# sensorCO2.net
KiCad netlist of a schematic drawn in EAGLE
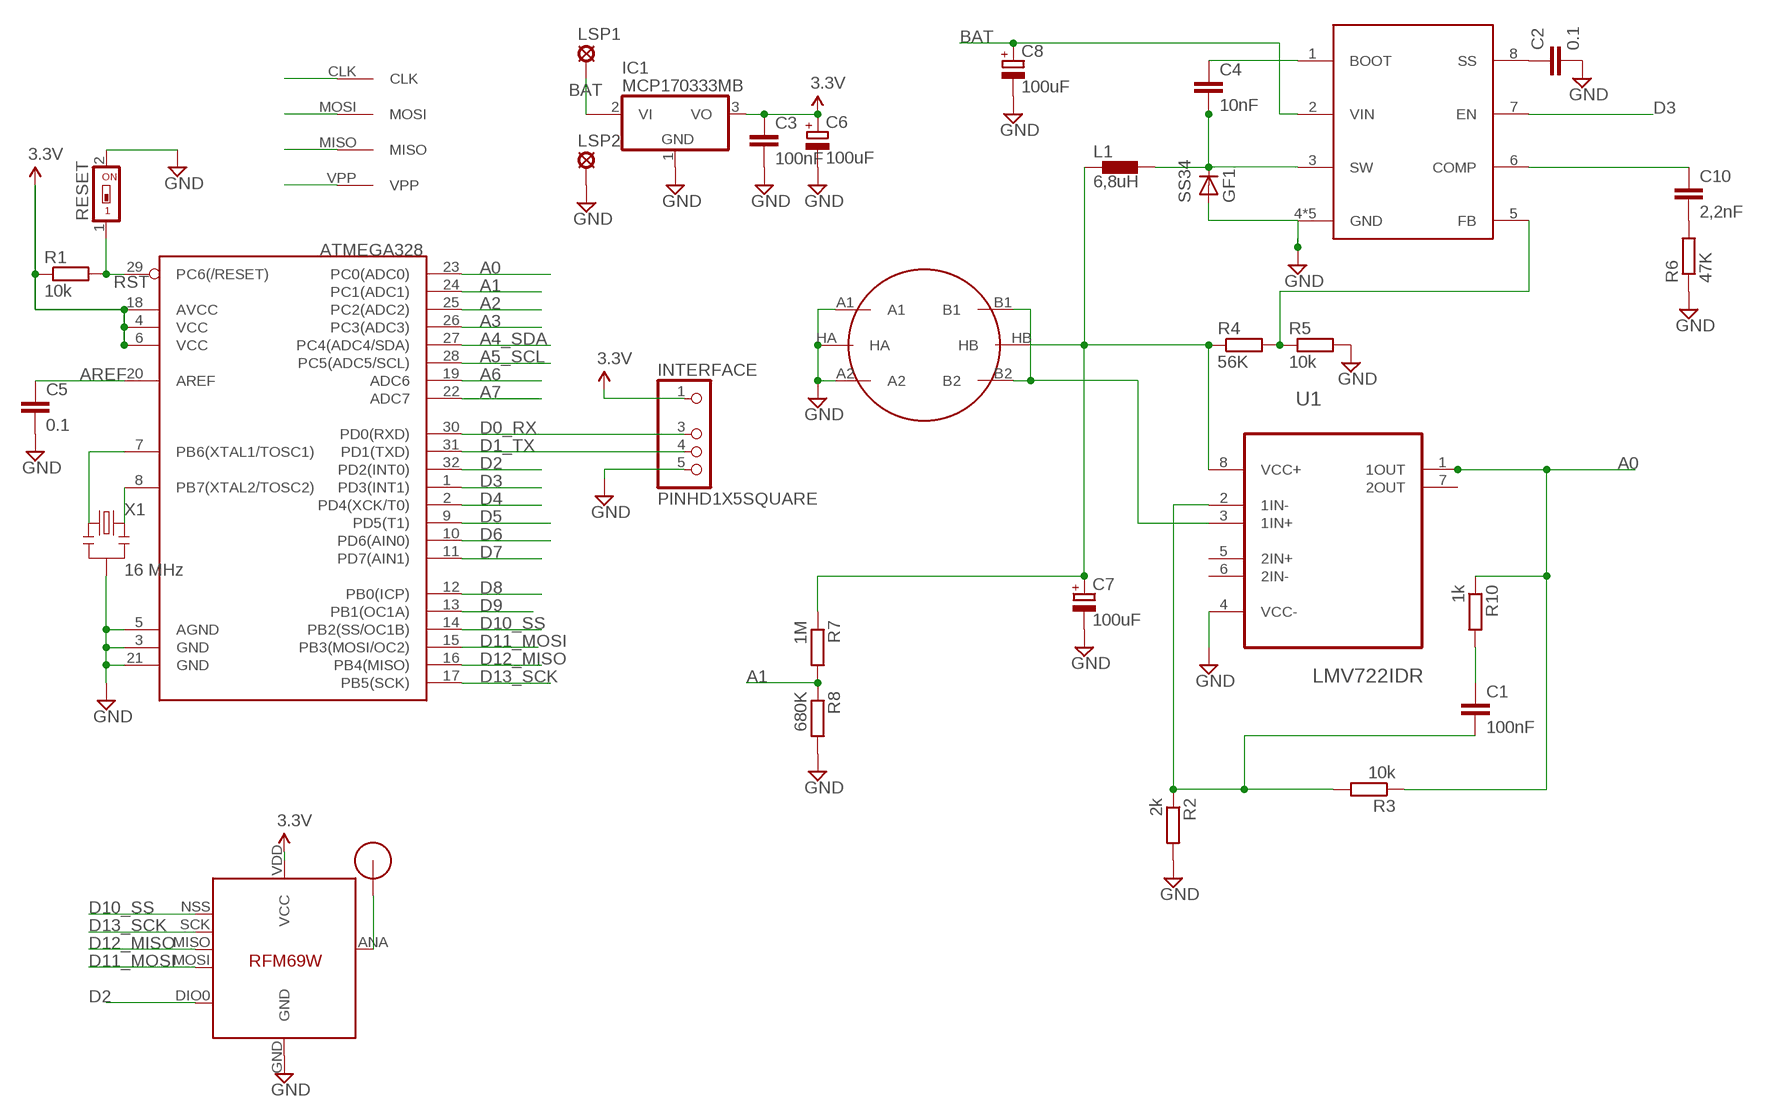
[diagram p0: schematic, sheet 1]

(export (version "E")
  (design (tool "Eeschema 10.0.6"))
  (components
    (comp (ref "ATMEGA328")
      (value "ATMega-328")
      (footprint "eagle-import:TQFP32-08")
      (libsource (lib "eagle-import") (part "ATMEGA168/328TQFP32"))
    )
    (comp (ref "C1")
      (value "100nF")
      (footprint "eagle-import:C2012")
      (libsource (lib "eagle-import") (part "C-EUC2012"))
    )
    (comp (ref "C2")
      (value "0.1")
      (footprint "eagle-import:C2012")
      (libsource (lib "eagle-import") (part "C-EUC2012"))
    )
    (comp (ref "C3")
      (value "100nF")
      (footprint "eagle-import:C2012")
      (libsource (lib "eagle-import") (part "C-EUC2012"))
    )
    (comp (ref "C4")
      (value "10nF")
      (footprint "eagle-import:C2012")
      (libsource (lib "eagle-import") (part "C-EUC2012"))
    )
    (comp (ref "C5")
      (value "0.1")
      (footprint "eagle-import:C2012")
      (libsource (lib "eagle-import") (part "C-EUC2012"))
    )
    (comp (ref "C6")
      (value "100uF")
      (footprint "eagle-import:SMC_B")
      (libsource (lib "eagle-import") (part "CPOL-EUSMCB"))
    )
    (comp (ref "C7")
      (value "100uF")
      (footprint "eagle-import:SMC_B")
      (libsource (lib "eagle-import") (part "CPOL-EUSMCB"))
    )
    (comp (ref "C8")
      (value "100uF")
      (footprint "eagle-import:SMC_B")
      (libsource (lib "eagle-import") (part "CPOL-EUSMCB"))
    )
    (comp (ref "C10")
      (value "2,2nF")
      (footprint "eagle-import:C2012")
      (libsource (lib "eagle-import") (part "C-EUC2012"))
    )
    (comp (ref "IC1")
      (value "MCP170333MB")
      (footprint "eagle-import:SOT89")
      (libsource (lib "eagle-import") (part "MCP1703MB33"))
    )
    (comp (ref "IC4")
      (value "RFM69")
      (footprint "eagle-import:RFM69W-MINPADS")
      (libsource (lib "eagle-import") (part "RFM69"))
    )
    (comp (ref "INTERFACE")
      (value "PINHD1X5SQUARE")
      (footprint "eagle-import:PINHD1X05-SQUARE")
      (libsource (lib "eagle-import") (part "PINHD1X5SQUARE"))
    )
    (comp (ref "L1")
      (value "6,8uH")
      (footprint "eagle-import:DR1030")
      (libsource (lib "eagle-import") (part "DR1030"))
    )
    (comp (ref "LSP1")
      (value "LSP11")
      (footprint "eagle-import:LSP11")
      (libsource (lib "eagle-import") (part "LSP11"))
    )
    (comp (ref "LSP2")
      (value "LSP11")
      (footprint "eagle-import:LSP11")
      (libsource (lib "eagle-import") (part "LSP11"))
    )
    (comp (ref "R1")
      (value "10k")
      (footprint "eagle-import:R2012")
      (libsource (lib "eagle-import") (part "R-EU_R2012"))
    )
    (comp (ref "R2")
      (value "2k")
      (footprint "eagle-import:R2012")
      (libsource (lib "eagle-import") (part "R-EU_R2012"))
    )
    (comp (ref "R3")
      (value "10k")
      (footprint "eagle-import:R2012")
      (libsource (lib "eagle-import") (part "R-EU_R2012"))
    )
    (comp (ref "R4")
      (value "56K")
      (footprint "eagle-import:R2012")
      (libsource (lib "eagle-import") (part "R-EU_R2012"))
    )
    (comp (ref "R5")
      (value "10k")
      (footprint "eagle-import:R2012")
      (libsource (lib "eagle-import") (part "R-EU_R2012"))
    )
    (comp (ref "R6")
      (value "47K")
      (footprint "eagle-import:R2012")
      (libsource (lib "eagle-import") (part "R-EU_R2012"))
    )
    (comp (ref "R7")
      (value "1M")
      (footprint "eagle-import:R2012")
      (libsource (lib "eagle-import") (part "R-EU_R2012"))
    )
    (comp (ref "R8")
      (value "680K")
      (footprint "eagle-import:R2012")
      (libsource (lib "eagle-import") (part "R-EU_R2012"))
    )
    (comp (ref "R10")
      (value "1k")
      (footprint "eagle-import:R2012")
      (libsource (lib "eagle-import") (part "R-EU_R2012"))
    )
    (comp (ref "RESET")
      (value "SWS001")
      (footprint "eagle-import:SMS-001")
      (libsource (lib "eagle-import") (part "SWS001"))
    )
    (comp (ref "SS34")
      (value "GF1")
      (footprint "eagle-import:SMA-DO214AC")
      (libsource (lib "eagle-import") (part "GF1"))
    )
    (comp (ref "U$1")
      (value "RFM12B_ANTENNA")
      (footprint "eagle-import:RFM12B-ANTENNA")
      (libsource (lib "eagle-import") (part "RFM12B_ANTENNA"))
    )
    (comp (ref "U$2")
      (value "AVRHEADERDIP")
      (footprint "eagle-import:AVRHEADER")
      (libsource (lib "eagle-import") (part "AVRHEADERDIP"))
    )
    (comp (ref "U$3")
      (value "RT8272")
      (footprint "eagle-import:RT8272")
      (libsource (lib "eagle-import") (part "RT8272"))
    )
    (comp (ref "U$4")
      (value "METHANE_SENSOR")
      (footprint "eagle-import:MQ-3")
      (libsource (lib "eagle-import") (part "METHANE_SENSOR"))
    )
    (comp (ref "U1")
      (value "LMV722IDR")
      (footprint "eagle-import:SOIC127P600X175-8N")
      (libsource (lib "eagle-import") (part "LMV722IDR"))
    )
    (comp (ref "X1")
      (value "16 MHz")
      (footprint "eagle-import:RESONATOR-SMD")
      (libsource (lib "eagle-import") (part "RESONATORSMD"))
    )
  )
  (nets
    (net (code "1") (name "/A0") (class "Default")
      (node (ref "ATMEGA328") (pin "23") (pinfunction "PC0(ADC0)_23") (pintype "bidirectional"))
      (node (ref "R10") (pin "1") (pinfunction "1_1") (pintype "passive"))
      (node (ref "R3") (pin "1") (pinfunction "1_1") (pintype "passive"))
      (node (ref "U1") (pin "1") (pinfunction "1OUT_1") (pintype "output"))
    )
    (net (code "2") (name "/A1") (class "Default")
      (node (ref "ATMEGA328") (pin "24") (pinfunction "PC1(ADC1)_24") (pintype "bidirectional"))
      (node (ref "R7") (pin "2") (pinfunction "2_2") (pintype "passive"))
      (node (ref "R8") (pin "1") (pinfunction "1_1") (pintype "passive"))
    )
    (net (code "3") (name "/A2") (class "Default")
      (node (ref "ATMEGA328") (pin "25") (pinfunction "PC2(ADC2)_25") (pintype "bidirectional"))
    )
    (net (code "4") (name "/A3") (class "Default")
      (node (ref "ATMEGA328") (pin "26") (pinfunction "PC3(ADC3)_26") (pintype "bidirectional"))
    )
    (net (code "5") (name "/A4_SDA") (class "Default")
      (node (ref "ATMEGA328") (pin "27") (pinfunction "PC4(ADC4/SDA)_27") (pintype "bidirectional"))
    )
    (net (code "6") (name "/A5_SCL") (class "Default")
      (node (ref "ATMEGA328") (pin "28") (pinfunction "PC5(ADC5/SCL)_28") (pintype "bidirectional"))
    )
    (net (code "7") (name "/A6") (class "Default")
      (node (ref "ATMEGA328") (pin "19") (pinfunction "ADC6_19") (pintype "bidirectional"))
    )
    (net (code "8") (name "/A7") (class "Default")
      (node (ref "ATMEGA328") (pin "22") (pinfunction "ADC7_22") (pintype "bidirectional"))
    )
    (net (code "9") (name "/AREF") (class "Default")
      (node (ref "ATMEGA328") (pin "20") (pinfunction "AREF_20") (pintype "bidirectional"))
      (node (ref "C5") (pin "1") (pinfunction "1_1") (pintype "passive"))
    )
    (net (code "10") (name "/BAT") (class "Default")
      (node (ref "C8") (pin "+") (pinfunction "+_+") (pintype "passive"))
      (node (ref "IC1") (pin "2@1") (pinfunction "VI1_2@1") (pintype "input"))
      (node (ref "LSP1") (pin "MP") (pinfunction "MP_MP") (pintype "passive"))
      (node (ref "U$3") (pin "2") (pinfunction "VIN_2") (pintype "bidirectional"))
    )
    (net (code "11") (name "/D0_RX") (class "Default")
      (node (ref "ATMEGA328") (pin "30") (pinfunction "PD0(RXD)_30") (pintype "bidirectional"))
      (node (ref "INTERFACE") (pin "3") (pinfunction "3_3") (pintype "passive"))
    )
    (net (code "12") (name "/D1_TX") (class "Default")
      (node (ref "ATMEGA328") (pin "31") (pinfunction "PD1(TXD)_31") (pintype "bidirectional"))
      (node (ref "INTERFACE") (pin "4") (pinfunction "4_4") (pintype "passive"))
    )
    (net (code "13") (name "/D2") (class "Default")
      (node (ref "ATMEGA328") (pin "32") (pinfunction "PD2(INT0)_32") (pintype "bidirectional"))
      (node (ref "IC4") (pin "DIO0") (pinfunction "DIO0_DIO0") (pintype "open_collector"))
    )
    (net (code "14") (name "/D3") (class "Default")
      (node (ref "ATMEGA328") (pin "1") (pinfunction "PD3(INT1)_1") (pintype "bidirectional"))
      (node (ref "U$3") (pin "7") (pinfunction "EN_7") (pintype "bidirectional"))
    )
    (net (code "15") (name "/D4") (class "Default")
      (node (ref "ATMEGA328") (pin "2") (pinfunction "PD4(XCK/T0)_2") (pintype "bidirectional"))
    )
    (net (code "16") (name "/D5") (class "Default")
      (node (ref "ATMEGA328") (pin "9") (pinfunction "PD5(T1)_9") (pintype "bidirectional"))
    )
    (net (code "17") (name "/D6") (class "Default")
      (node (ref "ATMEGA328") (pin "10") (pinfunction "PD6(AIN0)_10") (pintype "bidirectional"))
    )
    (net (code "18") (name "/D7") (class "Default")
      (node (ref "ATMEGA328") (pin "11") (pinfunction "PD7(AIN1)_11") (pintype "bidirectional"))
    )
    (net (code "19") (name "/D8") (class "Default")
      (node (ref "ATMEGA328") (pin "12") (pinfunction "PB0(ICP)_12") (pintype "bidirectional"))
    )
    (net (code "20") (name "/D9") (class "Default")
      (node (ref "ATMEGA328") (pin "13") (pinfunction "PB1(OC1A)_13") (pintype "bidirectional"))
    )
    (net (code "21") (name "/D10_SS") (class "Default")
      (node (ref "ATMEGA328") (pin "14") (pinfunction "PB2(SS/OC1B)_14") (pintype "bidirectional"))
      (node (ref "IC4") (pin "NSS") (pinfunction "SEL_NSS") (pintype "input"))
    )
    (net (code "22") (name "/D11_MOSI") (class "Default")
      (node (ref "ATMEGA328") (pin "15") (pinfunction "PB3(MOSI/OC2)_15") (pintype "bidirectional"))
      (node (ref "IC4") (pin "MOSI") (pinfunction "MOSI_MOSI") (pintype "output"))
      (node (ref "U$2") (pin "MOSI") (pinfunction "MOSI_MOSI") (pintype "bidirectional"))
    )
    (net (code "23") (name "/D12_MISO") (class "Default")
      (node (ref "ATMEGA328") (pin "16") (pinfunction "PB4(MISO)_16") (pintype "bidirectional"))
      (node (ref "IC4") (pin "MISO") (pinfunction "MISO_MISO") (pintype "input"))
      (node (ref "U$2") (pin "MISO") (pinfunction "MISO_MISO") (pintype "bidirectional"))
    )
    (net (code "24") (name "/D13_SCK") (class "Default")
      (node (ref "ATMEGA328") (pin "17") (pinfunction "PB5(SCK)_17") (pintype "bidirectional"))
      (node (ref "IC4") (pin "SCK") (pinfunction "SCK_SCK") (pintype "input"))
      (node (ref "U$2") (pin "CLK") (pinfunction "CLK_CLK") (pintype "bidirectional"))
    )
    (net (code "25") (name "/RST") (class "Default")
      (node (ref "ATMEGA328") (pin "29") (pinfunction "PC6(/RESET)_29") (pintype "bidirectional"))
      (node (ref "R1") (pin "2") (pinfunction "2_2") (pintype "passive"))
      (node (ref "RESET") (pin "1") (pinfunction "1_1") (pintype "passive"))
      (node (ref "U$2") (pin "VPP") (pinfunction "VPP_VPP") (pintype "bidirectional"))
    )
    (net (code "26") (name "3.3V") (class "Default")
      (node (ref "ATMEGA328") (pin "18") (pinfunction "AVCC_18") (pintype "bidirectional"))
      (node (ref "ATMEGA328") (pin "4") (pinfunction "VCC_4") (pintype "bidirectional"))
      (node (ref "ATMEGA328") (pin "6") (pinfunction "VCC_6") (pintype "bidirectional"))
      (node (ref "C3") (pin "1") (pinfunction "1_1") (pintype "passive"))
      (node (ref "C6") (pin "+") (pinfunction "+_+") (pintype "passive"))
      (node (ref "IC1") (pin "3") (pinfunction "VO_3") (pintype "passive"))
      (node (ref "IC4") (pin "VDD") (pinfunction "VCC_VDD") (pintype "power_in"))
      (node (ref "INTERFACE") (pin "1") (pinfunction "1_1") (pintype "passive"))
      (node (ref "R1") (pin "1") (pinfunction "1_1") (pintype "passive"))
    )
    (net (code "27") (name "GND") (class "Default")
      (node (ref "ATMEGA328") (pin "21") (pinfunction "GND_21") (pintype "bidirectional"))
      (node (ref "ATMEGA328") (pin "3") (pinfunction "GND_3") (pintype "bidirectional"))
      (node (ref "ATMEGA328") (pin "5") (pinfunction "AGND_5") (pintype "bidirectional"))
      (node (ref "C2") (pin "2") (pinfunction "2_2") (pintype "passive"))
      (node (ref "C3") (pin "2") (pinfunction "2_2") (pintype "passive"))
      (node (ref "C5") (pin "2") (pinfunction "2_2") (pintype "passive"))
      (node (ref "C6") (pin "-") (pinfunction "-_-") (pintype "passive"))
      (node (ref "C7") (pin "-") (pinfunction "-_-") (pintype "passive"))
      (node (ref "C8") (pin "-") (pinfunction "-_-") (pintype "passive"))
      (node (ref "IC1") (pin "1") (pinfunction "GND_1") (pintype "passive"))
      (node (ref "IC4") (pin "GND") (pinfunction "GND_GND") (pintype "power_in"))
      (node (ref "INTERFACE") (pin "5") (pinfunction "5_5") (pintype "passive"))
      (node (ref "LSP2") (pin "MP") (pinfunction "MP_MP") (pintype "passive"))
      (node (ref "R2") (pin "2") (pinfunction "2_2") (pintype "passive"))
      (node (ref "R5") (pin "2") (pinfunction "2_2") (pintype "passive"))
      (node (ref "R6") (pin "1") (pinfunction "1_1") (pintype "passive"))
      (node (ref "R8") (pin "2") (pinfunction "2_2") (pintype "passive"))
      (node (ref "RESET") (pin "2") (pinfunction "2_2") (pintype "passive"))
      (node (ref "SS34") (pin "A") (pinfunction "A_A") (pintype "passive"))
      (node (ref "U$3") (pin "4") (pinfunction "GND_4") (pintype "bidirectional"))
      (node (ref "U$3") (pin "P$1") (pinfunction "GND_P$1") (pintype "bidirectional"))
      (node (ref "U$3") (pin "P$2") (pinfunction "GND_P$2") (pintype "bidirectional"))
      (node (ref "U$3") (pin "P$3") (pinfunction "GND_P$3") (pintype "bidirectional"))
      (node (ref "U$3") (pin "P$4") (pinfunction "GND_P$4") (pintype "bidirectional"))
      (node (ref "U$4") (pin "A1") (pinfunction "A1_A1") (pintype "bidirectional"))
      (node (ref "U$4") (pin "A2") (pinfunction "A2_A2") (pintype "bidirectional"))
      (node (ref "U$4") (pin "HA") (pinfunction "HA_HA") (pintype "bidirectional"))
      (node (ref "U1") (pin "4") (pinfunction "VCC-_4") (pintype "power_in"))
      (node (ref "X1") (pin "2") (pinfunction "2_2") (pintype "passive"))
    )
    (net (code "28") (name "Net-(ATMEGA328-PB6(XTAL1{slash}TOSC1))") (class "Default")
      (node (ref "ATMEGA328") (pin "7") (pinfunction "PB6(XTAL1/TOSC1)_7") (pintype "bidirectional"))
      (node (ref "X1") (pin "1") (pinfunction "1_1") (pintype "passive"))
    )
    (net (code "29") (name "Net-(ATMEGA328-PB7(XTAL2{slash}TOSC2))") (class "Default")
      (node (ref "ATMEGA328") (pin "8") (pinfunction "PB7(XTAL2/TOSC2)_8") (pintype "bidirectional"))
      (node (ref "X1") (pin "3") (pinfunction "3_3") (pintype "passive"))
    )
    (net (code "30") (name "Net-(C1-Pad1)") (class "Default")
      (node (ref "C1") (pin "1") (pinfunction "1_1") (pintype "passive"))
      (node (ref "R10") (pin "2") (pinfunction "2_2") (pintype "passive"))
    )
    (net (code "31") (name "Net-(C10-Pad2)") (class "Default")
      (node (ref "C10") (pin "2") (pinfunction "2_2") (pintype "passive"))
      (node (ref "R6") (pin "2") (pinfunction "2_2") (pintype "passive"))
    )
    (net (code "32") (name "Net-(IC4-ANT)") (class "Default")
      (node (ref "IC4") (pin "ANA") (pinfunction "ANT_ANA") (pintype "passive"))
      (node (ref "U$1") (pin "P$1") (pinfunction "1_P$1") (pintype "bidirectional"))
    )
    (net (code "33") (name "Net-(SS34-C)") (class "Default")
      (node (ref "C4") (pin "2") (pinfunction "2_2") (pintype "passive"))
      (node (ref "L1") (pin "2") (pinfunction "2_2") (pintype "passive"))
      (node (ref "SS34") (pin "K") (pinfunction "C_K") (pintype "passive"))
      (node (ref "U$3") (pin "3") (pinfunction "SW_3") (pintype "bidirectional"))
    )
    (net (code "34") (name "Net-(U$3-BOOT)") (class "Default")
      (node (ref "C4") (pin "1") (pinfunction "1_1") (pintype "passive"))
      (node (ref "U$3") (pin "1") (pinfunction "BOOT_1") (pintype "bidirectional"))
    )
    (net (code "35") (name "Net-(U$3-COMP)") (class "Default")
      (node (ref "C10") (pin "1") (pinfunction "1_1") (pintype "passive"))
      (node (ref "U$3") (pin "6") (pinfunction "COMP_6") (pintype "bidirectional"))
    )
    (net (code "36") (name "Net-(U$3-FB)") (class "Default")
      (node (ref "R4") (pin "2") (pinfunction "2_2") (pintype "passive"))
      (node (ref "R5") (pin "1") (pinfunction "1_1") (pintype "passive"))
      (node (ref "U$3") (pin "5") (pinfunction "FB_5") (pintype "bidirectional"))
    )
    (net (code "37") (name "Net-(U$3-SS)") (class "Default")
      (node (ref "C2") (pin "1") (pinfunction "1_1") (pintype "passive"))
      (node (ref "U$3") (pin "8") (pinfunction "SS_8") (pintype "bidirectional"))
    )
    (net (code "38") (name "Net-(U1-1IN+)") (class "Default")
      (node (ref "U$4") (pin "B1") (pinfunction "B1_B1") (pintype "bidirectional"))
      (node (ref "U$4") (pin "B2") (pinfunction "B2_B2") (pintype "bidirectional"))
      (node (ref "U1") (pin "3") (pinfunction "1IN+_3") (pintype "input"))
    )
    (net (code "39") (name "Net-(U1-1IN-)") (class "Default")
      (node (ref "C1") (pin "2") (pinfunction "2_2") (pintype "passive"))
      (node (ref "R2") (pin "1") (pinfunction "1_1") (pintype "passive"))
      (node (ref "R3") (pin "2") (pinfunction "2_2") (pintype "passive"))
      (node (ref "U1") (pin "2") (pinfunction "1IN-_2") (pintype "input"))
    )
    (net (code "40") (name "Net-(U1-VCC+)") (class "Default")
      (node (ref "C7") (pin "+") (pinfunction "+_+") (pintype "passive"))
      (node (ref "L1") (pin "1") (pinfunction "1_1") (pintype "passive"))
      (node (ref "R4") (pin "1") (pinfunction "1_1") (pintype "passive"))
      (node (ref "R7") (pin "1") (pinfunction "1_1") (pintype "passive"))
      (node (ref "U$4") (pin "HB") (pinfunction "HB_HB") (pintype "bidirectional"))
      (node (ref "U1") (pin "8") (pinfunction "VCC+_8") (pintype "power_in"))
    )
    (net (code "41") (name "unconnected-(IC1-VI-Pad2)") (class "Default")
      (node (ref "IC1") (pin "2") (pinfunction "VI_2") (pintype "input"))
    )
    (net (code "42") (name "unconnected-(U1-2IN+-Pad5)") (class "Default")
      (node (ref "U1") (pin "5") (pinfunction "2IN+_5") (pintype "input"))
    )
    (net (code "43") (name "unconnected-(U1-2IN--Pad6)") (class "Default")
      (node (ref "U1") (pin "6") (pinfunction "2IN-_6") (pintype "input"))
    )
    (net (code "44") (name "unconnected-(U1-2OUT-Pad7)") (class "Default")
      (node (ref "U1") (pin "7") (pinfunction "2OUT_7") (pintype "output"))
    )
  )
)
